# buffer.net
KiCad netlist of a schematic drawn in Altium Designer
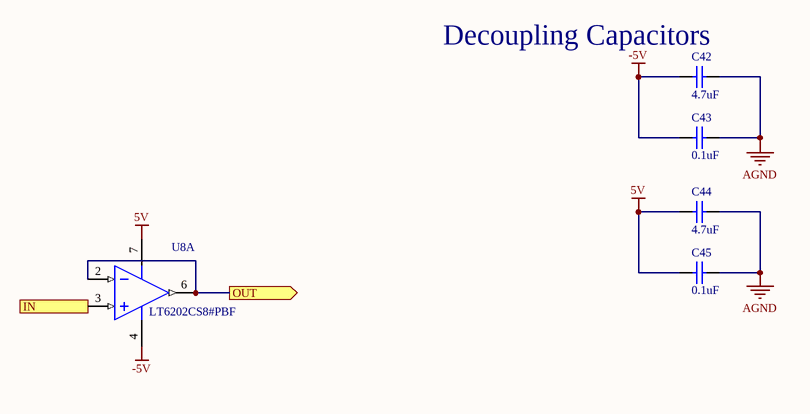
[diagram p0: buffer.SchDoc]

(export (version "E")
  (design (tool "Eeschema 10.0.6"))
  (components
    (comp (ref "C42")
      (value "4.7uF")
      (footprint "0402_Cap")
      (description "Capacitor, 4.7uF, 0805")
      (libsource (lib "Arturo_Approved") (part "CL21A475KAQNNNE"))
    )
    (comp (ref "C43")
      (value "0.1uF")
      (footprint "0402_Cap")
      (description "Capacitor, 0.1uF, 0805")
      (libsource (lib "Arturo_Approved") (part "CL21B104KACNNNC"))
    )
    (comp (ref "C44")
      (value "4.7uF")
      (footprint "0402_Cap")
      (description "Capacitor, 4.7uF, 0805")
      (libsource (lib "Arturo_Approved") (part "CL21A475KAQNNNE"))
    )
    (comp (ref "C45")
      (value "0.1uF")
      (footprint "0402_Cap")
      (description "Capacitor, 0.1uF, 0805")
      (libsource (lib "Arturo_Approved") (part "CL21B104KACNNNC"))
    )
    (comp (ref "U8")
      (value "LT6202CS8#PBF")
      (footprint "LT-S8-8_N")
      (fields
        (field (name "LINEAR TECHNOLOGY PART NUMBER") "LT6202")
        (field (name "MANUFACTURER") "Linear Technology")
      )
      (libsource (lib "Altium Content Vault") (part "LT-LT149X-LT1XX2-8"))
    )
  )
  (nets
    (net (code "1") (name "-5V") (class "Default")
      (node (ref "C42") (pin "1") (pinfunction "1_1") (pintype "passive"))
      (node (ref "C43") (pin "1") (pinfunction "1_1") (pintype "passive"))
      (node (ref "U8") (pin "4") (pinfunction "V-_4") (pintype "power_in"))
    )
    (net (code "2") (name "/IN") (class "Default")
      (node (ref "U8") (pin "3") (pinfunction "+IN_3") (pintype "input"))
    )
    (net (code "3") (name "/OUT") (class "Default")
      (node (ref "U8") (pin "2") (pinfunction "-IN_2") (pintype "input"))
      (node (ref "U8") (pin "6") (pinfunction "OUT_6") (pintype "output"))
    )
    (net (code "4") (name "5V") (class "Default")
      (node (ref "C44") (pin "1") (pinfunction "1_1") (pintype "passive"))
      (node (ref "C45") (pin "1") (pinfunction "1_1") (pintype "passive"))
      (node (ref "U8") (pin "7") (pinfunction "V+_7") (pintype "power_in"))
    )
    (net (code "5") (name "AGND") (class "Default")
      (node (ref "C42") (pin "2") (pinfunction "2_2") (pintype "passive"))
      (node (ref "C43") (pin "2") (pinfunction "2_2") (pintype "passive"))
      (node (ref "C44") (pin "2") (pinfunction "2_2") (pintype "passive"))
      (node (ref "C45") (pin "2") (pinfunction "2_2") (pintype "passive"))
    )
  )
)
